# PiBoard.net
KiCad netlist of a schematic drawn in EAGLE
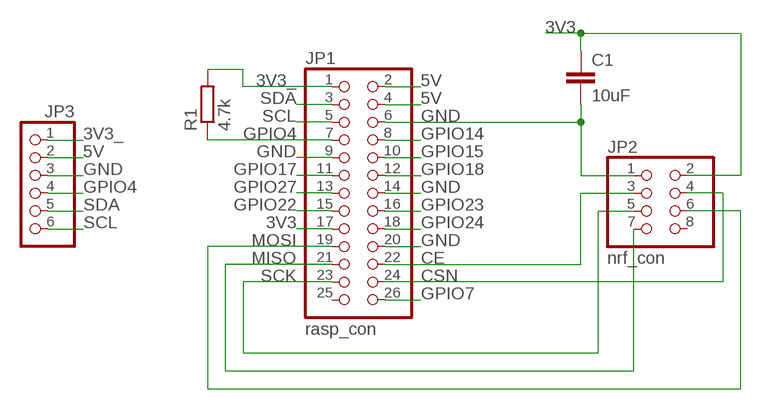
[diagram p0: schematic, sheet 1]

(export (version "E")
  (design (tool "Eeschema 10.0.6"))
  (components
    (comp (ref "C1")
      (value "10uF")
      (footprint "eagle-import:1206")
      (libsource (lib "eagle-import") (part "CAP1206"))
    )
    (comp (ref "JP1")
      (value "rasp_con")
      (footprint "eagle-import:2X13")
      (libsource (lib "eagle-import") (part "PINHD-2X13"))
    )
    (comp (ref "JP2")
      (value "nrf_con")
      (footprint "eagle-import:2X04")
      (libsource (lib "eagle-import") (part "PINHD-2X4"))
    )
    (comp (ref "JP3")
      (value "PINHD-1X6")
      (footprint "eagle-import:1X06")
      (libsource (lib "eagle-import") (part "PINHD-1X6"))
    )
    (comp (ref "R1")
      (value "4.7k")
      (footprint "eagle-import:R1206")
      (libsource (lib "eagle-import") (part "R-EU_R1206"))
    )
  )
  (nets
    (net (code "1") (name "/3V3") (class "Default")
      (node (ref "C1") (pin "1") (pinfunction "1_1") (pintype "passive"))
      (node (ref "JP1") (pin "17") (pinfunction "17_17") (pintype "passive"))
      (node (ref "JP2") (pin "2") (pinfunction "2_2") (pintype "passive"))
    )
    (net (code "2") (name "/3V3_") (class "Default")
      (node (ref "JP1") (pin "1") (pinfunction "1_1") (pintype "passive"))
      (node (ref "JP3") (pin "1") (pinfunction "1_1") (pintype "passive"))
      (node (ref "R1") (pin "2") (pinfunction "2_2") (pintype "passive"))
    )
    (net (code "3") (name "/5V") (class "Default")
      (node (ref "JP1") (pin "2") (pinfunction "2_2") (pintype "passive"))
      (node (ref "JP1") (pin "4") (pinfunction "4_4") (pintype "passive"))
      (node (ref "JP3") (pin "2") (pinfunction "2_2") (pintype "passive"))
    )
    (net (code "4") (name "/CE") (class "Default")
      (node (ref "JP1") (pin "22") (pinfunction "22_22") (pintype "passive"))
      (node (ref "JP2") (pin "3") (pinfunction "3_3") (pintype "passive"))
    )
    (net (code "5") (name "/CSN") (class "Default")
      (node (ref "JP1") (pin "24") (pinfunction "24_24") (pintype "passive"))
      (node (ref "JP2") (pin "4") (pinfunction "4_4") (pintype "passive"))
    )
    (net (code "6") (name "/GND") (class "Default")
      (node (ref "C1") (pin "2") (pinfunction "2_2") (pintype "passive"))
      (node (ref "JP1") (pin "14") (pinfunction "14_14") (pintype "passive"))
      (node (ref "JP1") (pin "20") (pinfunction "20_20") (pintype "passive"))
      (node (ref "JP1") (pin "6") (pinfunction "6_6") (pintype "passive"))
      (node (ref "JP1") (pin "9") (pinfunction "9_9") (pintype "passive"))
      (node (ref "JP2") (pin "1") (pinfunction "1_1") (pintype "passive"))
      (node (ref "JP3") (pin "3") (pinfunction "3_3") (pintype "passive"))
    )
    (net (code "7") (name "/GPIO4") (class "Default")
      (node (ref "JP1") (pin "7") (pinfunction "7_7") (pintype "passive"))
      (node (ref "JP3") (pin "4") (pinfunction "4_4") (pintype "passive"))
      (node (ref "R1") (pin "1") (pinfunction "1_1") (pintype "passive"))
    )
    (net (code "8") (name "/GPIO7") (class "Default")
      (node (ref "JP1") (pin "26") (pinfunction "26_26") (pintype "passive"))
    )
    (net (code "9") (name "/GPIO14") (class "Default")
      (node (ref "JP1") (pin "8") (pinfunction "8_8") (pintype "passive"))
    )
    (net (code "10") (name "/GPIO15") (class "Default")
      (node (ref "JP1") (pin "10") (pinfunction "10_10") (pintype "passive"))
    )
    (net (code "11") (name "/GPIO17") (class "Default")
      (node (ref "JP1") (pin "11") (pinfunction "11_11") (pintype "passive"))
    )
    (net (code "12") (name "/GPIO18") (class "Default")
      (node (ref "JP1") (pin "12") (pinfunction "12_12") (pintype "passive"))
    )
    (net (code "13") (name "/GPIO22") (class "Default")
      (node (ref "JP1") (pin "15") (pinfunction "15_15") (pintype "passive"))
    )
    (net (code "14") (name "/GPIO23") (class "Default")
      (node (ref "JP1") (pin "16") (pinfunction "16_16") (pintype "passive"))
    )
    (net (code "15") (name "/GPIO24") (class "Default")
      (node (ref "JP1") (pin "18") (pinfunction "18_18") (pintype "passive"))
    )
    (net (code "16") (name "/GPIO27") (class "Default")
      (node (ref "JP1") (pin "13") (pinfunction "13_13") (pintype "passive"))
    )
    (net (code "17") (name "/MISO") (class "Default")
      (node (ref "JP1") (pin "21") (pinfunction "21_21") (pintype "passive"))
      (node (ref "JP2") (pin "7") (pinfunction "7_7") (pintype "passive"))
    )
    (net (code "18") (name "/MOSI") (class "Default")
      (node (ref "JP1") (pin "19") (pinfunction "19_19") (pintype "passive"))
      (node (ref "JP2") (pin "6") (pinfunction "6_6") (pintype "passive"))
    )
    (net (code "19") (name "/SCK") (class "Default")
      (node (ref "JP1") (pin "23") (pinfunction "23_23") (pintype "passive"))
      (node (ref "JP2") (pin "5") (pinfunction "5_5") (pintype "passive"))
    )
    (net (code "20") (name "/SCL") (class "Default")
      (node (ref "JP1") (pin "5") (pinfunction "5_5") (pintype "passive"))
      (node (ref "JP3") (pin "6") (pinfunction "6_6") (pintype "passive"))
    )
    (net (code "21") (name "/SDA") (class "Default")
      (node (ref "JP1") (pin "3") (pinfunction "3_3") (pintype "passive"))
      (node (ref "JP3") (pin "5") (pinfunction "5_5") (pintype "passive"))
    )
    (net (code "22") (name "unconnected-(JP1-Pad25)") (class "Default")
      (node (ref "JP1") (pin "25") (pinfunction "25_25") (pintype "passive"))
    )
    (net (code "23") (name "unconnected-(JP2-Pad8)") (class "Default")
      (node (ref "JP2") (pin "8") (pinfunction "8_8") (pintype "passive"))
    )
  )
)
